# EasyEDA_v2_b.net
KiCad netlist of a schematic drawn in EasyEDA
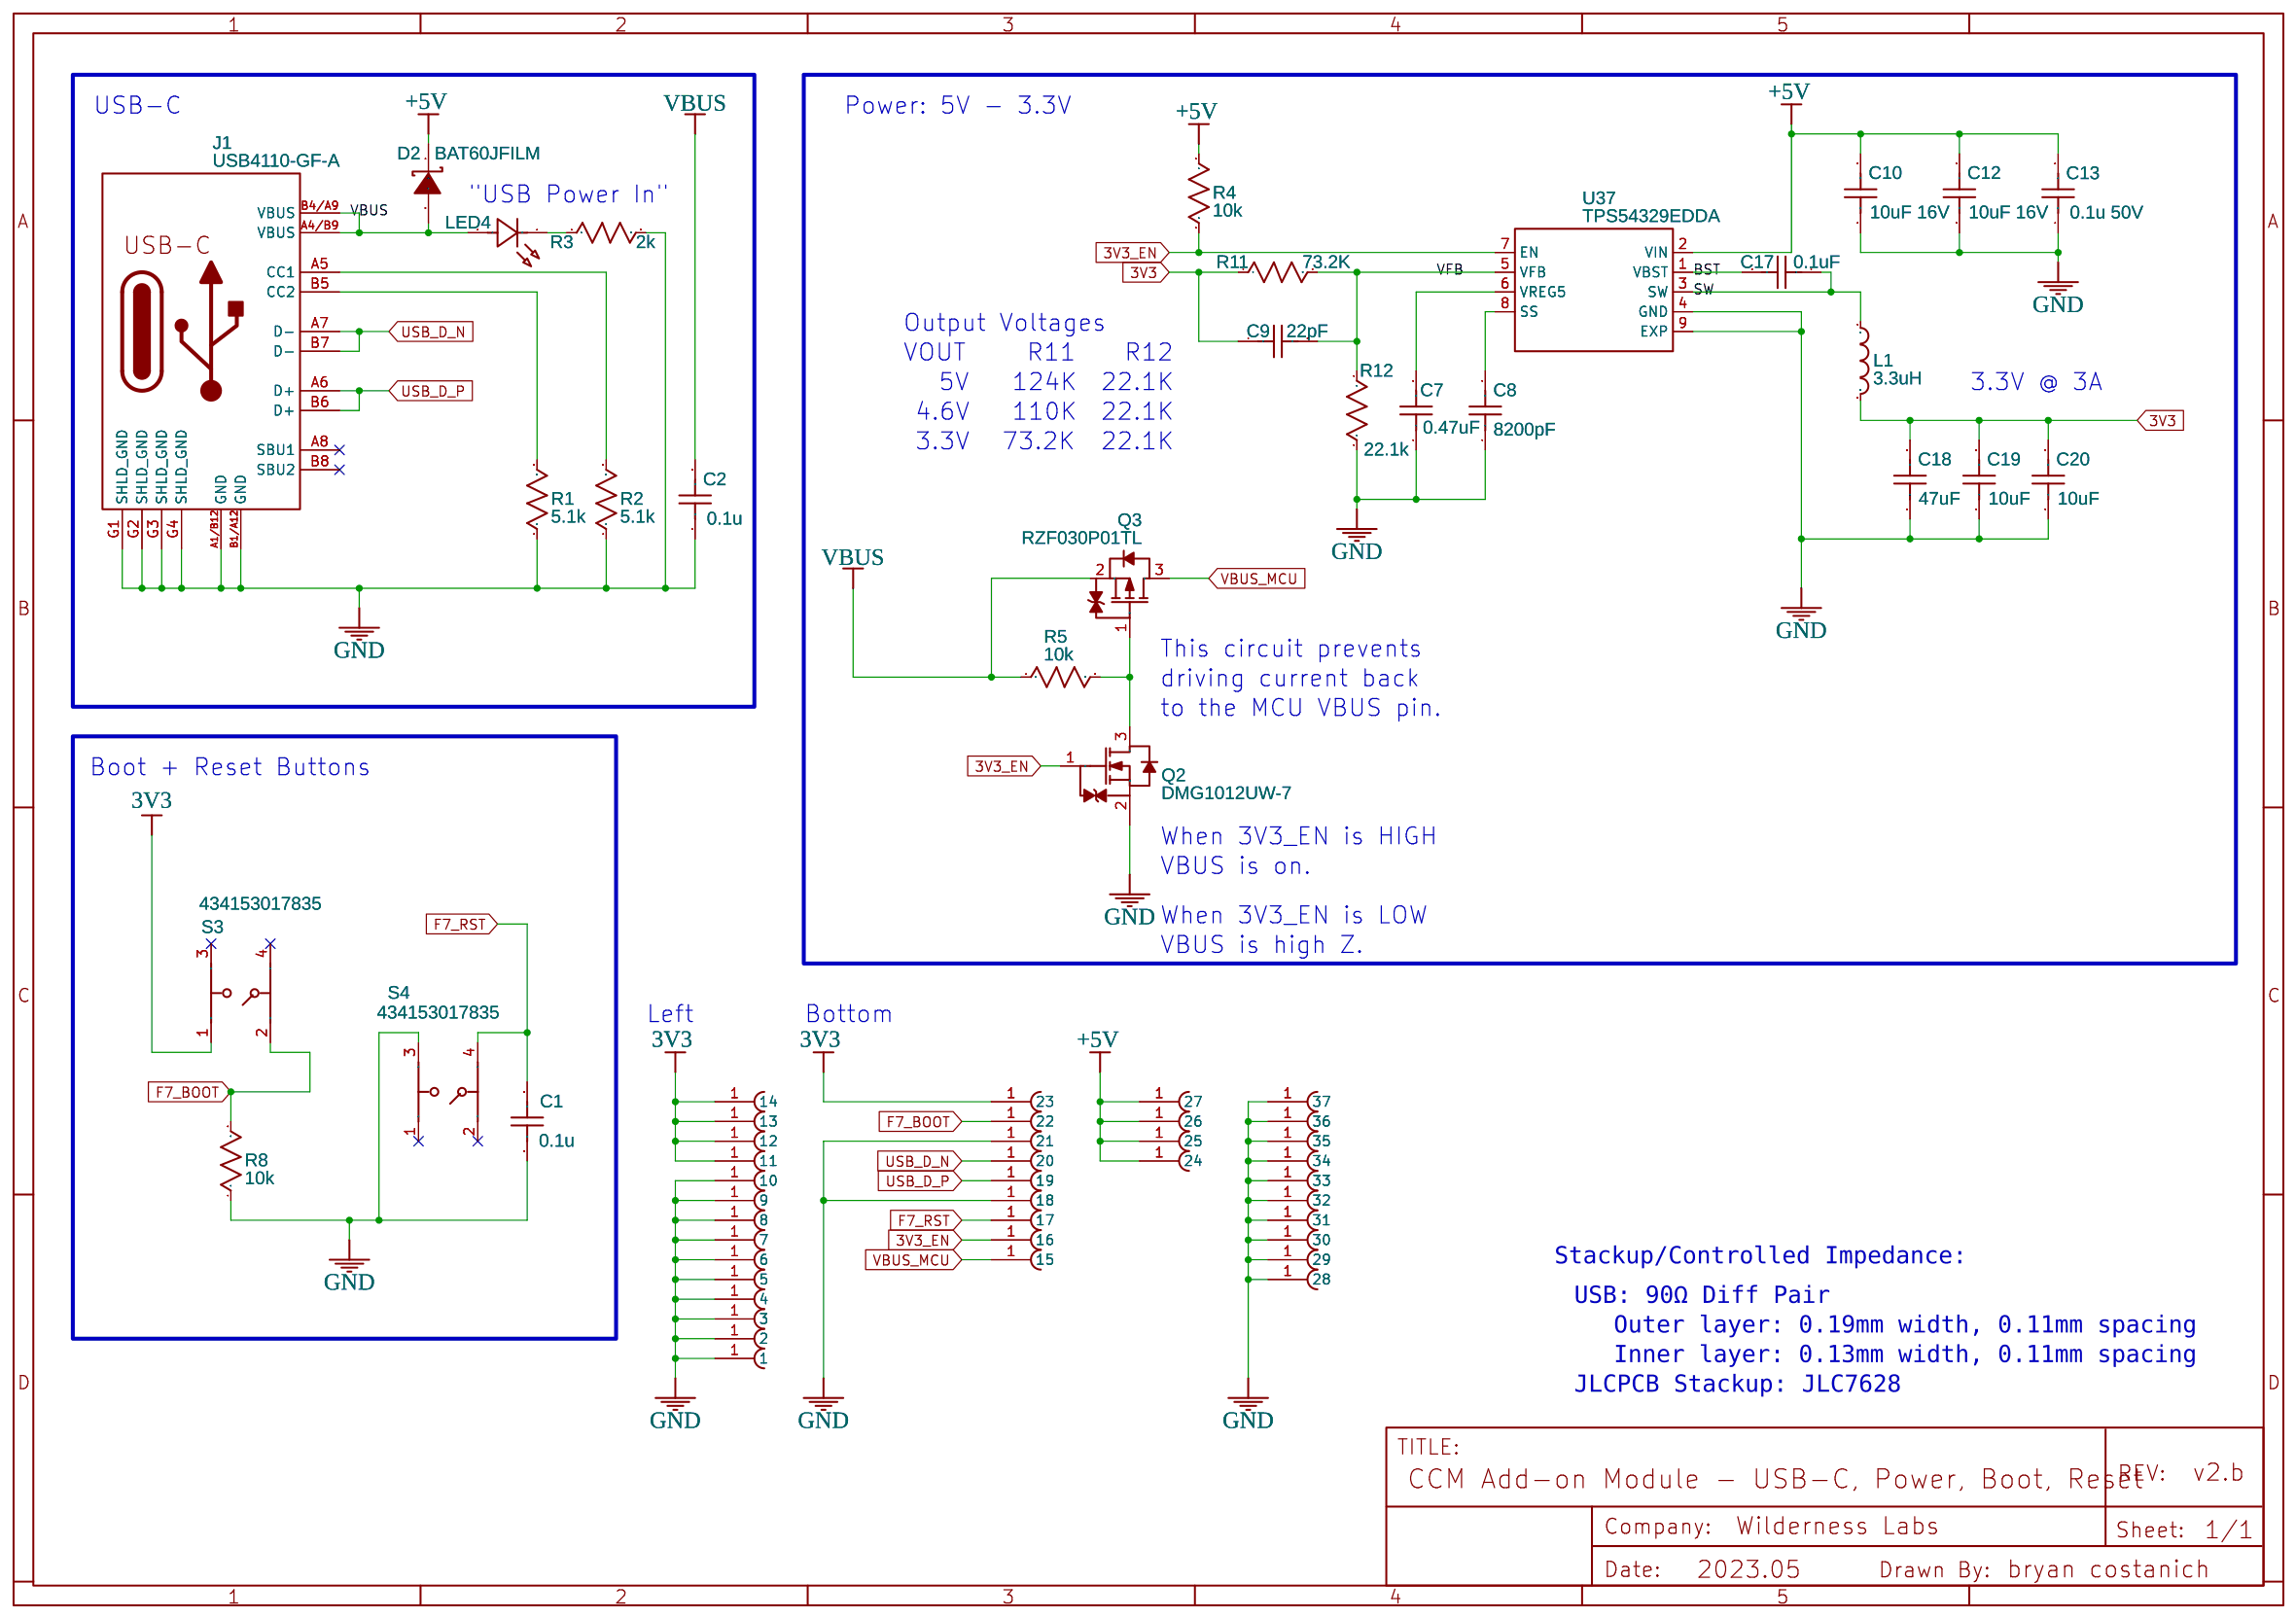
[diagram p0: schematic sheet]

(export (version "E")
  (design (tool "Eeschema 10.0.6"))
  (components
    (comp (ref "C1")
      (value "0.1u")
      (fields (field (name "BOM_Manufacturer Part") "CC0603KRX7R7BB104"))
      (libsource (lib "") (part "C_0603_US"))
    )
    (comp (ref "C2")
      (value "0.1u")
      (fields (field (name "BOM_Manufacturer Part") "CC0603KRX7R9BB103"))
      (libsource (lib "") (part "C_0402_US"))
    )
    (comp (ref "C7")
      (value "0.47uF")
      (fields (field (name "BOM_Manufacturer Part") "CC0603KRX7R8BB474"))
      (libsource (lib "") (part "C_0402_US"))
    )
    (comp (ref "C8")
      (value "8200pF")
      (fields (field (name "BOM_Manufacturer Part") "CC0603KRX7R9BB822"))
      (libsource (lib "") (part "C_0603_US"))
    )
    (comp (ref "C9")
      (value "22pF")
      (fields (field (name "BOM_Manufacturer Part") "CC0603JRNPO9BN220"))
      (libsource (lib "") (part "C_0603_US_1"))
    )
    (comp (ref "C10")
      (value "10uF 16V")
      (fields (field (name "BOM_Manufacturer Part") "CC0805KRX5R7BB106"))
      (libsource (lib "") (part "C_0805_US"))
    )
    (comp (ref "C12")
      (value "10uF 16V")
      (fields (field (name "BOM_Manufacturer Part") "CC0805KRX5R7BB106"))
      (libsource (lib "") (part "C_0805_US"))
    )
    (comp (ref "C13")
      (value "0.1u 50V")
      (fields (field (name "BOM_Manufacturer Part") "CC0603KRX7R9BB103"))
      (libsource (lib "") (part "C_0402_US"))
    )
    (comp (ref "C17")
      (value "0.1uF")
      (fields (field (name "BOM_Manufacturer Part") "CC0603KRX7R9BB103"))
      (libsource (lib "") (part "C_0402_US_1"))
    )
    (comp (ref "C18")
      (value "47uF")
      (fields (field (name "BOM_Manufacturer Part") "GRM32ER71A476ME15L"))
      (libsource (lib "") (part "C_0402_US"))
    )
    (comp (ref "C19")
      (value "10uF")
      (fields (field (name "BOM_Manufacturer Part") "CC0805KRX5R7BB106"))
      (libsource (lib "") (part "C_0805_US"))
    )
    (comp (ref "C20")
      (value "10uF")
      (fields (field (name "BOM_Manufacturer Part") "CC0805KRX5R7BB106"))
      (libsource (lib "") (part "C_0805_US"))
    )
    (comp (ref "D2")
      (value "BAT60JFILM")
      (fields (field (name "BOM_Supplier Part") "C133103"))
      (libsource (lib "") (part "BAT60JFILM"))
    )
    (comp (ref "J1")
      (value "USB4110-GF-A")
      (fields (field (name "BOM_Manufacturer Part") "USB4105-GF-A"))
      (libsource (lib "") (part "USB4110-GF-A"))
    )
    (comp (ref "L1")
      (value "3.3uH")
      (fields
        (field (name "BOM_Manufacturer Part") "NRS5040T3R3NMGJ")
        (field (name "BOM_Supplier Part") "C222946")
      )
      (libsource (lib "") (part "NRS5040T3R3NMGJ"))
    )
    (comp (ref "LED4") (value "EAST16083BA0") (libsource (lib "") (part "EAST16083BA0")))
    (comp (ref "Q2")
      (value "DMG1012UW-7")
      (fields (field (name "BOM_Supplier Part") "C156390"))
      (libsource (lib "") (part "DMG1012UW-7"))
    )
    (comp (ref "Q3")
      (value "RZF030P01TL")
      (fields (field (name "BOM_Supplier Part") "C2941618"))
      (libsource (lib "") (part "RZF030P01TL"))
    )
    (comp (ref "R1")
      (value "5.1k")
      (fields (field (name "BOM_Manufacturer Part") "RC0603FR-075K1L"))
      (libsource (lib "") (part "R_0603_US_1"))
    )
    (comp (ref "R2")
      (value "5.1k")
      (fields (field (name "BOM_Manufacturer Part") "RC0603FR-075K1L"))
      (libsource (lib "") (part "R_0603_US_1"))
    )
    (comp (ref "R3")
      (value "2k")
      (fields (field (name "BOM_Manufacturer Part") "RC0603FR-072KL"))
      (libsource (lib "") (part "R_0603_US"))
    )
    (comp (ref "R4")
      (value "10k")
      (fields (field (name "BOM_Manufacturer Part") "RC0603FR-0710KL"))
      (libsource (lib "") (part "R_0603_US_2"))
    )
    (comp (ref "R5")
      (value "10k")
      (fields (field (name "BOM_Manufacturer Part") "RC0603FR-0710KL"))
      (libsource (lib "") (part "R_0603_US"))
    )
    (comp (ref "R8")
      (value "10k")
      (fields (field (name "BOM_Manufacturer Part") "RC0603FR-0710KL"))
      (libsource (lib "") (part "R_0603_US_1"))
    )
    (comp (ref "R11")
      (value "73.2K")
      (fields (field (name "BOM_Manufacturer Part") "RC0603FR-0773K2L"))
      (libsource (lib "") (part "R_0603_US"))
    )
    (comp (ref "R12")
      (value "22.1k")
      (fields (field (name "BOM_Manufacturer Part") "RC0603FR-0722K1L"))
      (libsource (lib "") (part "R_0603_US_1"))
    )
    (comp (ref "S3") (value "434153017835") (libsource (lib "") (part "434153017835")))
    (comp (ref "S4") (value "434153017835") (libsource (lib "") (part "434153017835")))
    (comp (ref "U1") (value "1.2MM SMT Castellation") (libsource (lib "") (part "1.2MM SMT Castellation_5")))
    (comp (ref "U2") (value "1.2MM SMT Castellation") (libsource (lib "") (part "1.2MM SMT Castellation_16")))
    (comp (ref "U3") (value "1.2MM SMT Castellation") (libsource (lib "") (part "1.2MM SMT Castellation_10")))
    (comp (ref "U5") (value "1.2MM SMT Castellation") (libsource (lib "") (part "1.2MM SMT Castellation_20")))
    (comp (ref "U6") (value "1.2MM SMT Castellation") (libsource (lib "") (part "1.2MM SMT Castellation")))
    (comp (ref "U7") (value "1.2MM SMT Castellation") (libsource (lib "") (part "1.2MM SMT Castellation_23")))
    (comp (ref "U8") (value "1.2MM SMT Castellation") (libsource (lib "") (part "1.2MM SMT Castellation_1")))
    (comp (ref "U9") (value "1.2MM SMT Castellation") (libsource (lib "") (part "1.2MM SMT Castellation_34")))
    (comp (ref "U10")
      (value "1.2MM SMT Castellation")
      (libsource (lib "") (part "1.2MM SMT Castellation_14"))
    )
    (comp (ref "U11")
      (value "1.2MM SMT Castellation")
      (libsource (lib "") (part "1.2MM SMT Castellation_22"))
    )
    (comp (ref "U12")
      (value "1.2MM SMT Castellation")
      (libsource (lib "") (part "1.2MM SMT Castellation_28"))
    )
    (comp (ref "U13")
      (value "1.2MM SMT Castellation")
      (libsource (lib "") (part "1.2MM SMT Castellation_13"))
    )
    (comp (ref "U14")
      (value "1.2MM SMT Castellation")
      (libsource (lib "") (part "1.2MM SMT Castellation_21"))
    )
    (comp (ref "U15")
      (value "1.2MM SMT Castellation")
      (libsource (lib "") (part "1.2MM SMT Castellation_36"))
    )
    (comp (ref "U16")
      (value "1.2MM SMT Castellation")
      (libsource (lib "") (part "1.2MM SMT Castellation_27"))
    )
    (comp (ref "U17") (value "1.2MM SMT Castellation") (libsource (lib "") (part "1.2MM SMT Castellation_8")))
    (comp (ref "U18") (value "1.2MM SMT Castellation") (libsource (lib "") (part "1.2MM SMT Castellation_4")))
    (comp (ref "U19") (value "1.2MM SMT Castellation") (libsource (lib "") (part "1.2MM SMT Castellation_3")))
    (comp (ref "U20")
      (value "1.2MM SMT Castellation")
      (libsource (lib "") (part "1.2MM SMT Castellation_19"))
    )
    (comp (ref "U21")
      (value "1.2MM SMT Castellation")
      (libsource (lib "") (part "1.2MM SMT Castellation_35"))
    )
    (comp (ref "U22")
      (value "1.2MM SMT Castellation")
      (libsource (lib "") (part "1.2MM SMT Castellation_25"))
    )
    (comp (ref "U23")
      (value "1.2MM SMT Castellation")
      (libsource (lib "") (part "1.2MM SMT Castellation_17"))
    )
    (comp (ref "U24") (value "1.2MM SMT Castellation") (libsource (lib "") (part "1.2MM SMT Castellation_7")))
    (comp (ref "U25") (value "1.2MM SMT Castellation") (libsource (lib "") (part "1.2MM SMT Castellation_2")))
    (comp (ref "U26")
      (value "1.2MM SMT Castellation")
      (libsource (lib "") (part "1.2MM SMT Castellation_15"))
    )
    (comp (ref "U27")
      (value "1.2MM SMT Castellation")
      (libsource (lib "") (part "1.2MM SMT Castellation_24"))
    )
    (comp (ref "U28")
      (value "1.2MM SMT Castellation")
      (libsource (lib "") (part "1.2MM SMT Castellation_18"))
    )
    (comp (ref "U29") (value "1.2MM SMT Castellation") (libsource (lib "") (part "1.2MM SMT Castellation_6")))
    (comp (ref "U30")
      (value "1.2MM SMT Castellation")
      (libsource (lib "") (part "1.2MM SMT Castellation_12"))
    )
    (comp (ref "U31")
      (value "1.2MM SMT Castellation")
      (libsource (lib "") (part "1.2MM SMT Castellation_11"))
    )
    (comp (ref "U32")
      (value "1.2MM SMT Castellation")
      (libsource (lib "") (part "1.2MM SMT Castellation_30"))
    )
    (comp (ref "U33")
      (value "1.2MM SMT Castellation")
      (libsource (lib "") (part "1.2MM SMT Castellation_33"))
    )
    (comp (ref "U34")
      (value "1.2MM SMT Castellation")
      (libsource (lib "") (part "1.2MM SMT Castellation_26"))
    )
    (comp (ref "U35") (value "1.2MM SMT Castellation") (libsource (lib "") (part "1.2MM SMT Castellation_9")))
    (comp (ref "U36")
      (value "1.2MM SMT Castellation")
      (libsource (lib "") (part "1.2MM SMT Castellation_32"))
    )
    (comp (ref "U37")
      (value "TPS54329EDDA")
      (fields (field (name "BOM_Supplier Part") "C38344"))
      (libsource (lib "") (part "TPS54329EDDAR LOGICAL"))
    )
    (comp (ref "U39")
      (value "1.2MM SMT Castellation")
      (libsource (lib "") (part "1.2MM SMT Castellation_29"))
    )
    (comp (ref "U53")
      (value "1.2MM SMT Castellation")
      (libsource (lib "") (part "1.2MM SMT Castellation_31"))
    )
  )
  (nets
    (net (code "1") (name "+5V") (class "Default")
      (node (ref "C10") (pin "2") (pinfunction "2_2") (pintype "unspecified"))
      (node (ref "C12") (pin "2") (pinfunction "2_2") (pintype "unspecified"))
      (node (ref "C13") (pin "2") (pinfunction "2_2") (pintype "unspecified"))
      (node (ref "D2") (pin "1") (pinfunction "K_1") (pintype "unspecified"))
      (node (ref "R4") (pin "1") (pinfunction "1_1") (pintype "unspecified"))
      (node (ref "U2") (pin "1") (pinfunction "25_1") (pintype "unspecified"))
      (node (ref "U24") (pin "1") (pinfunction "26_1") (pintype "unspecified"))
      (node (ref "U26") (pin "1") (pinfunction "27_1") (pintype "unspecified"))
      (node (ref "U29") (pin "1") (pinfunction "24_1") (pintype "unspecified"))
      (node (ref "U37") (pin "2") (pinfunction "VIN_2") (pintype "unspecified"))
    )
    (net (code "2") (name "/BST") (class "Default")
      (node (ref "C17") (pin "2") (pinfunction "2_2") (pintype "unspecified"))
      (node (ref "U37") (pin "1") (pinfunction "VBST_1") (pintype "unspecified"))
    )
    (net (code "3") (name "/SW") (class "Default")
      (node (ref "C17") (pin "1") (pinfunction "1_1") (pintype "unspecified"))
      (node (ref "L1") (pin "1") (pinfunction "1_1") (pintype "unspecified"))
      (node (ref "U37") (pin "3") (pinfunction "SW_3") (pintype "unspecified"))
    )
    (net (code "4") (name "/VFB") (class "Default")
      (node (ref "C9") (pin "2") (pinfunction "2_2") (pintype "unspecified"))
      (node (ref "R11") (pin "2") (pinfunction "2_2") (pintype "unspecified"))
      (node (ref "R12") (pin "2") (pinfunction "2_2") (pintype "unspecified"))
      (node (ref "U37") (pin "5") (pinfunction "VFB_5") (pintype "unspecified"))
    )
    (net (code "5") (name "3V3") (class "Default")
      (node (ref "C18") (pin "2") (pinfunction "2_2") (pintype "unspecified"))
      (node (ref "C19") (pin "2") (pinfunction "2_2") (pintype "unspecified"))
      (node (ref "C20") (pin "2") (pinfunction "2_2") (pintype "unspecified"))
      (node (ref "C9") (pin "1") (pinfunction "1_1") (pintype "unspecified"))
      (node (ref "L1") (pin "2") (pinfunction "2_2") (pintype "unspecified"))
      (node (ref "R11") (pin "1") (pinfunction "1_1") (pintype "unspecified"))
      (node (ref "S3") (pin "1") (pinfunction "1_1") (pintype "unspecified"))
      (node (ref "U13") (pin "1") (pinfunction "14_1") (pintype "unspecified"))
      (node (ref "U14") (pin "1") (pinfunction "13_1") (pintype "unspecified"))
      (node (ref "U15") (pin "1") (pinfunction "12_1") (pintype "unspecified"))
      (node (ref "U16") (pin "1") (pinfunction "11_1") (pintype "unspecified"))
      (node (ref "U23") (pin "1") (pinfunction "23_1") (pintype "unspecified"))
    )
    (net (code "6") (name "3V3_EN") (class "Default")
      (node (ref "Q2") (pin "1") (pinfunction "G_1") (pintype "unspecified"))
      (node (ref "R4") (pin "2") (pinfunction "2_2") (pintype "unspecified"))
      (node (ref "U22") (pin "1") (pinfunction "16_1") (pintype "unspecified"))
      (node (ref "U37") (pin "7") (pinfunction "EN_7") (pintype "unspecified"))
    )
    (net (code "7") (name "F7_BOOT") (class "Default")
      (node (ref "R8") (pin "2") (pinfunction "2_2") (pintype "unspecified"))
      (node (ref "S3") (pin "2") (pinfunction "2_2") (pintype "unspecified"))
      (node (ref "U27") (pin "1") (pinfunction "22_1") (pintype "unspecified"))
    )
    (net (code "8") (name "F7_RST") (class "Default")
      (node (ref "C1") (pin "2") (pinfunction "2_2") (pintype "unspecified"))
      (node (ref "S4") (pin "4") (pinfunction "4_4") (pintype "unspecified"))
      (node (ref "U21") (pin "1") (pinfunction "17_1") (pintype "unspecified"))
    )
    (net (code "9") (name "GND") (class "Default")
      (node (ref "C1") (pin "1") (pinfunction "1_1") (pintype "unspecified"))
      (node (ref "C10") (pin "1") (pinfunction "1_1") (pintype "unspecified"))
      (node (ref "C12") (pin "1") (pinfunction "1_1") (pintype "unspecified"))
      (node (ref "C13") (pin "1") (pinfunction "1_1") (pintype "unspecified"))
      (node (ref "C18") (pin "1") (pinfunction "1_1") (pintype "unspecified"))
      (node (ref "C19") (pin "1") (pinfunction "1_1") (pintype "unspecified"))
      (node (ref "C2") (pin "1") (pinfunction "1_1") (pintype "unspecified"))
      (node (ref "C20") (pin "1") (pinfunction "1_1") (pintype "unspecified"))
      (node (ref "C7") (pin "1") (pinfunction "1_1") (pintype "unspecified"))
      (node (ref "C8") (pin "1") (pinfunction "1_1") (pintype "unspecified"))
      (node (ref "J1") (pin "A1/B12") (pinfunction "GND_A1/B12") (pintype "passive"))
      (node (ref "J1") (pin "B1/A12") (pinfunction "GND_B1/A12") (pintype "passive"))
      (node (ref "J1") (pin "G1") (pinfunction "SHLD_GND_G1") (pintype "passive"))
      (node (ref "J1") (pin "G2") (pinfunction "SHLD_GND_G2") (pintype "passive"))
      (node (ref "J1") (pin "G3") (pinfunction "SHLD_GND_G3") (pintype "passive"))
      (node (ref "J1") (pin "G4") (pinfunction "SHLD_GND_G4") (pintype "passive"))
      (node (ref "Q2") (pin "2") (pinfunction "S_2") (pintype "unspecified"))
      (node (ref "R1") (pin "1") (pinfunction "1_1") (pintype "unspecified"))
      (node (ref "R12") (pin "1") (pinfunction "1_1") (pintype "unspecified"))
      (node (ref "R2") (pin "1") (pinfunction "1_1") (pintype "unspecified"))
      (node (ref "R3") (pin "2") (pinfunction "2_2") (pintype "unspecified"))
      (node (ref "R8") (pin "1") (pinfunction "1_1") (pintype "unspecified"))
      (node (ref "S4") (pin "3") (pinfunction "3_3") (pintype "unspecified"))
      (node (ref "U1") (pin "1") (pinfunction "2_1") (pintype "unspecified"))
      (node (ref "U10") (pin "1") (pinfunction "7_1") (pintype "unspecified"))
      (node (ref "U11") (pin "1") (pinfunction "6_1") (pintype "unspecified"))
      (node (ref "U19") (pin "1") (pinfunction "18_1") (pintype "unspecified"))
      (node (ref "U20") (pin "1") (pinfunction "28_1") (pintype "unspecified"))
      (node (ref "U25") (pin "1") (pinfunction "31_1") (pintype "unspecified"))
      (node (ref "U28") (pin "1") (pinfunction "21_1") (pintype "unspecified"))
      (node (ref "U3") (pin "1") (pinfunction "3_1") (pintype "unspecified"))
      (node (ref "U30") (pin "1") (pinfunction "30_1") (pintype "unspecified"))
      (node (ref "U31") (pin "1") (pinfunction "29_1") (pintype "unspecified"))
      (node (ref "U32") (pin "1") (pinfunction "32_1") (pintype "unspecified"))
      (node (ref "U33") (pin "1") (pinfunction "35_1") (pintype "unspecified"))
      (node (ref "U34") (pin "1") (pinfunction "34_1") (pintype "unspecified"))
      (node (ref "U35") (pin "1") (pinfunction "33_1") (pintype "unspecified"))
      (node (ref "U36") (pin "1") (pinfunction "36_1") (pintype "unspecified"))
      (node (ref "U37") (pin "4") (pinfunction "GND_4") (pintype "unspecified"))
      (node (ref "U37") (pin "9") (pinfunction "EXP_9") (pintype "unspecified"))
      (node (ref "U39") (pin "1") (pinfunction "37_1") (pintype "unspecified"))
      (node (ref "U5") (pin "1") (pinfunction "4_1") (pintype "unspecified"))
      (node (ref "U53") (pin "1") (pinfunction "1_1") (pintype "unspecified"))
      (node (ref "U6") (pin "1") (pinfunction "5_1") (pintype "unspecified"))
      (node (ref "U7") (pin "1") (pinfunction "10_1") (pintype "unspecified"))
      (node (ref "U8") (pin "1") (pinfunction "9_1") (pintype "unspecified"))
      (node (ref "U9") (pin "1") (pinfunction "8_1") (pintype "unspecified"))
    )
    (net (code "10") (name "Net-(J1-CC1)") (class "Default")
      (node (ref "J1") (pin "A5") (pinfunction "CC1_A5") (pintype "unspecified"))
      (node (ref "R2") (pin "2") (pinfunction "2_2") (pintype "unspecified"))
    )
    (net (code "11") (name "Net-(J1-CC2)") (class "Default")
      (node (ref "J1") (pin "B5") (pinfunction "CC2_B5") (pintype "unspecified"))
      (node (ref "R1") (pin "2") (pinfunction "2_2") (pintype "unspecified"))
    )
    (net (code "12") (name "Net-(LED4-K)") (class "Default")
      (node (ref "LED4") (pin "1") (pinfunction "K_1") (pintype "unspecified"))
      (node (ref "R3") (pin "1") (pinfunction "1_1") (pintype "unspecified"))
    )
    (net (code "13") (name "Net-(Q2-D)") (class "Default")
      (node (ref "Q2") (pin "3") (pinfunction "D_3") (pintype "unspecified"))
      (node (ref "Q3") (pin "1") (pinfunction "G_1") (pintype "unspecified"))
      (node (ref "R5") (pin "2") (pinfunction "2_2") (pintype "unspecified"))
    )
    (net (code "14") (name "Net-(U37-SS)") (class "Default")
      (node (ref "C8") (pin "2") (pinfunction "2_2") (pintype "unspecified"))
      (node (ref "U37") (pin "8") (pinfunction "SS_8") (pintype "unspecified"))
    )
    (net (code "15") (name "Net-(U37-VREG5)") (class "Default")
      (node (ref "C7") (pin "2") (pinfunction "2_2") (pintype "unspecified"))
      (node (ref "U37") (pin "6") (pinfunction "VREG5_6") (pintype "unspecified"))
    )
    (net (code "16") (name "USB_D_N") (class "Default")
      (node (ref "J1") (pin "A7") (pinfunction "D-_A7") (pintype "unspecified"))
      (node (ref "J1") (pin "B7") (pinfunction "D-_B7") (pintype "unspecified"))
      (node (ref "U17") (pin "1") (pinfunction "20_1") (pintype "unspecified"))
    )
    (net (code "17") (name "USB_D_P") (class "Default")
      (node (ref "J1") (pin "A6") (pinfunction "D+_A6") (pintype "unspecified"))
      (node (ref "J1") (pin "B6") (pinfunction "D+_B6") (pintype "unspecified"))
      (node (ref "U18") (pin "1") (pinfunction "19_1") (pintype "unspecified"))
    )
    (net (code "18") (name "VBUS") (class "Default")
      (node (ref "C2") (pin "2") (pinfunction "2_2") (pintype "unspecified"))
      (node (ref "D2") (pin "2") (pinfunction "A_2") (pintype "unspecified"))
      (node (ref "J1") (pin "A4/B9") (pinfunction "VBUS_A4/B9") (pintype "unspecified"))
      (node (ref "J1") (pin "B4/A9") (pinfunction "VBUS_B4/A9") (pintype "unspecified"))
      (node (ref "LED4") (pin "2") (pinfunction "A_2") (pintype "unspecified"))
      (node (ref "Q3") (pin "2") (pinfunction "S_2") (pintype "unspecified"))
      (node (ref "R5") (pin "1") (pinfunction "1_1") (pintype "unspecified"))
    )
    (net (code "19") (name "VBUS_MCU") (class "Default")
      (node (ref "Q3") (pin "3") (pinfunction "D_3") (pintype "unspecified"))
      (node (ref "U12") (pin "1") (pinfunction "15_1") (pintype "unspecified"))
    )
    (net (code "20") (name "unconnected-(J1-SBU1-PadA8)") (class "Default")
      (node (ref "J1") (pin "A8") (pinfunction "SBU1_A8") (pintype "unspecified+no_connect"))
    )
    (net (code "21") (name "unconnected-(J1-SBU2-PadB8)") (class "Default")
      (node (ref "J1") (pin "B8") (pinfunction "SBU2_B8") (pintype "unspecified+no_connect"))
    )
    (net (code "22") (name "unconnected-(S3-Pad3)") (class "Default")
      (node (ref "S3") (pin "3") (pinfunction "3_3") (pintype "unspecified+no_connect"))
    )
    (net (code "23") (name "unconnected-(S3-Pad4)") (class "Default")
      (node (ref "S3") (pin "4") (pinfunction "4_4") (pintype "unspecified+no_connect"))
    )
    (net (code "24") (name "unconnected-(S4-Pad1)") (class "Default")
      (node (ref "S4") (pin "1") (pinfunction "1_1") (pintype "unspecified+no_connect"))
    )
    (net (code "25") (name "unconnected-(S4-Pad2)") (class "Default")
      (node (ref "S4") (pin "2") (pinfunction "2_2") (pintype "unspecified+no_connect"))
    )
  )
)
